# Remote.net
KiCad netlist of a schematic drawn in EAGLE
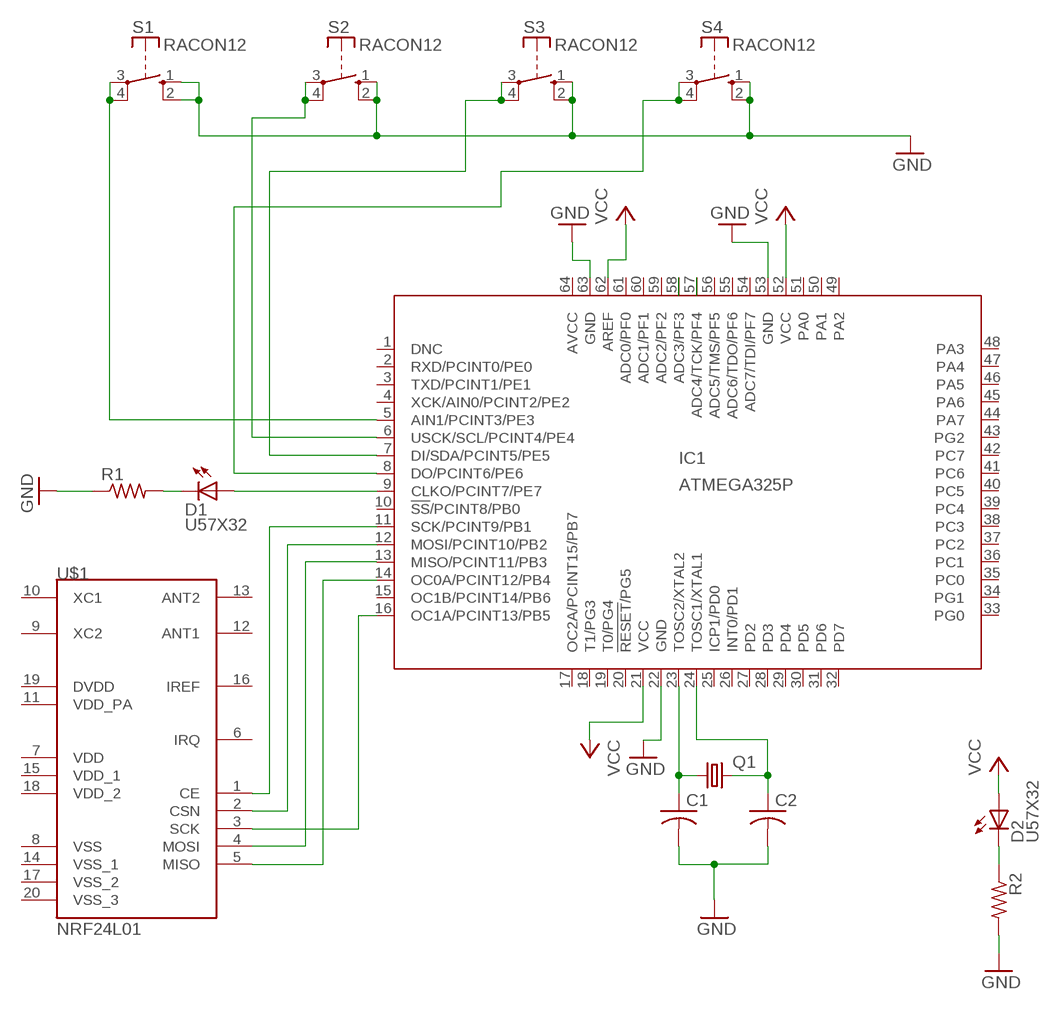
[diagram p0: schematic, sheet 1]

(export (version "E")
  (design (tool "Eeschema 10.0.6"))
  (components
    (comp (ref "C1")
      (value "C-US025-024X044")
      (footprint "eagle-import:C025-024X044")
      (libsource (lib "eagle-import") (part "C-US025-024X044"))
    )
    (comp (ref "C2")
      (value "C-US025-024X044")
      (footprint "eagle-import:C025-024X044")
      (libsource (lib "eagle-import") (part "C-US025-024X044"))
    )
    (comp (ref "D1")
      (value "U57X32")
      (footprint "eagle-import:U57X32")
      (libsource (lib "eagle-import") (part "U57X32"))
    )
    (comp (ref "D2")
      (value "U57X32")
      (footprint "eagle-import:U57X32")
      (libsource (lib "eagle-import") (part "U57X32"))
    )
    (comp (ref "IC1")
      (value "ATMEGA325P")
      (footprint "eagle-import:64M1")
      (fields (field (name "MPN") "ATMEGA325PV-10AU"))
      (libsource (lib "eagle-import") (part "ATMEGA325P"))
    )
    (comp (ref "Q1")
      (value "CRYSTALHC49S")
      (footprint "eagle-import:HC49_S")
      (libsource (lib "eagle-import") (part "CRYSTALHC49S"))
    )
    (comp (ref "R1")
      (value "R-US_0204/5")
      (footprint "eagle-import:0204_5")
      (libsource (lib "eagle-import") (part "R-US_0204/5"))
    )
    (comp (ref "R2")
      (value "R-US_0204/5")
      (footprint "eagle-import:0204_5")
      (libsource (lib "eagle-import") (part "R-US_0204/5"))
    )
    (comp (ref "S1")
      (value "RACON12")
      (footprint "eagle-import:RACON12")
      (libsource (lib "eagle-import") (part "RACON12"))
    )
    (comp (ref "S2")
      (value "RACON12")
      (footprint "eagle-import:RACON12")
      (libsource (lib "eagle-import") (part "RACON12"))
    )
    (comp (ref "S3")
      (value "RACON12")
      (footprint "eagle-import:RACON12")
      (libsource (lib "eagle-import") (part "RACON12"))
    )
    (comp (ref "S4")
      (value "RACON12")
      (footprint "eagle-import:RACON12")
      (libsource (lib "eagle-import") (part "RACON12"))
    )
    (comp (ref "U$1")
      (value "NRF24L01")
      (footprint "eagle-import:QFN20")
      (libsource (lib "eagle-import") (part "NRF24L01"))
    )
  )
  (nets
    (net (code "1") (name "/AVCC") (class "Default")
      (node (ref "IC1") (pin "64") (pinfunction "AVCC_64") (pintype "power_in"))
    )
    (net (code "2") (name "GND") (class "Default")
      (node (ref "C1") (pin "2") (pinfunction "2_2") (pintype "passive"))
      (node (ref "C2") (pin "2") (pinfunction "2_2") (pintype "passive"))
      (node (ref "IC1") (pin "22") (pinfunction "GND_22") (pintype "power_in"))
      (node (ref "IC1") (pin "53") (pinfunction "GND_53") (pintype "power_in"))
      (node (ref "IC1") (pin "63") (pinfunction "GND_63") (pintype "power_in"))
      (node (ref "R1") (pin "1") (pinfunction "1_1") (pintype "passive"))
      (node (ref "R2") (pin "2") (pinfunction "2_2") (pintype "passive"))
      (node (ref "S1") (pin "1") (pinfunction "S_1") (pintype "passive"))
      (node (ref "S1") (pin "2") (pinfunction "S_2") (pintype "passive"))
      (node (ref "S2") (pin "1") (pinfunction "S_1") (pintype "passive"))
      (node (ref "S2") (pin "2") (pinfunction "S_2") (pintype "passive"))
      (node (ref "S3") (pin "1") (pinfunction "S_1") (pintype "passive"))
      (node (ref "S3") (pin "2") (pinfunction "S_2") (pintype "passive"))
      (node (ref "S4") (pin "1") (pinfunction "S_1") (pintype "passive"))
      (node (ref "S4") (pin "2") (pinfunction "S_2") (pintype "passive"))
    )
    (net (code "3") (name "Net-(D1-C)") (class "Default")
      (node (ref "D1") (pin "K") (pinfunction "C_K") (pintype "passive"))
      (node (ref "R1") (pin "2") (pinfunction "2_2") (pintype "passive"))
    )
    (net (code "4") (name "Net-(D2-C)") (class "Default")
      (node (ref "D2") (pin "K") (pinfunction "C_K") (pintype "passive"))
      (node (ref "R2") (pin "1") (pinfunction "1_1") (pintype "passive"))
    )
    (net (code "5") (name "Net-(IC1-AIN1{slash}PCINT3{slash}PE3)") (class "Default")
      (node (ref "IC1") (pin "5") (pinfunction "AIN1/PCINT3/PE3_5") (pintype "bidirectional"))
      (node (ref "S1") (pin "3") (pinfunction "P_3") (pintype "passive"))
      (node (ref "S1") (pin "4") (pinfunction "P_4") (pintype "passive"))
    )
    (net (code "6") (name "Net-(IC1-CLKO{slash}PCINT7{slash}PE7)") (class "Default")
      (node (ref "D1") (pin "A") (pinfunction "A_A") (pintype "passive"))
      (node (ref "IC1") (pin "9") (pinfunction "CLKO/PCINT7/PE7_9") (pintype "bidirectional"))
    )
    (net (code "7") (name "Net-(IC1-DI{slash}SDA{slash}PCINT5{slash}PE5)") (class "Default")
      (node (ref "IC1") (pin "7") (pinfunction "DI/SDA/PCINT5/PE5_7") (pintype "bidirectional"))
      (node (ref "S3") (pin "3") (pinfunction "P_3") (pintype "passive"))
      (node (ref "S3") (pin "4") (pinfunction "P_4") (pintype "passive"))
    )
    (net (code "8") (name "Net-(IC1-DO{slash}PCINT6{slash}PE6)") (class "Default")
      (node (ref "IC1") (pin "8") (pinfunction "DO/PCINT6/PE6_8") (pintype "bidirectional"))
      (node (ref "S4") (pin "3") (pinfunction "P_3") (pintype "passive"))
      (node (ref "S4") (pin "4") (pinfunction "P_4") (pintype "passive"))
    )
    (net (code "9") (name "Net-(IC1-MISO{slash}PCINT11{slash}PB3)") (class "Default")
      (node (ref "IC1") (pin "13") (pinfunction "MISO/PCINT11/PB3_13") (pintype "bidirectional"))
      (node (ref "U$1") (pin "4") (pinfunction "MOSI_4") (pintype "bidirectional"))
    )
    (net (code "10") (name "Net-(IC1-MOSI{slash}PCINT10{slash}PB2)") (class "Default")
      (node (ref "IC1") (pin "12") (pinfunction "MOSI/PCINT10/PB2_12") (pintype "bidirectional"))
      (node (ref "U$1") (pin "2") (pinfunction "CSN_2") (pintype "bidirectional"))
    )
    (net (code "11") (name "Net-(IC1-OC0A{slash}PCINT12{slash}PB4)") (class "Default")
      (node (ref "IC1") (pin "14") (pinfunction "OC0A/PCINT12/PB4_14") (pintype "bidirectional"))
      (node (ref "U$1") (pin "5") (pinfunction "MISO_5") (pintype "bidirectional"))
    )
    (net (code "12") (name "Net-(IC1-OC1A{slash}PCINT13{slash}PB5)") (class "Default")
      (node (ref "IC1") (pin "16") (pinfunction "OC1A/PCINT13/PB5_16") (pintype "bidirectional"))
      (node (ref "U$1") (pin "3") (pinfunction "SCK_3") (pintype "bidirectional"))
    )
    (net (code "13") (name "Net-(IC1-SCK{slash}PCINT9{slash}PB1)") (class "Default")
      (node (ref "IC1") (pin "11") (pinfunction "SCK/PCINT9/PB1_11") (pintype "bidirectional"))
      (node (ref "U$1") (pin "1") (pinfunction "CE_1") (pintype "bidirectional"))
    )
    (net (code "14") (name "Net-(IC1-TOSC1{slash}XTAL1)") (class "Default")
      (node (ref "C2") (pin "1") (pinfunction "1_1") (pintype "passive"))
      (node (ref "IC1") (pin "24") (pinfunction "TOSC1/XTAL1_24") (pintype "input"))
      (node (ref "Q1") (pin "2") (pinfunction "2_2") (pintype "passive"))
    )
    (net (code "15") (name "Net-(IC1-TOSC2{slash}XTAL2)") (class "Default")
      (node (ref "C1") (pin "1") (pinfunction "1_1") (pintype "passive"))
      (node (ref "IC1") (pin "23") (pinfunction "TOSC2/XTAL2_23") (pintype "output"))
      (node (ref "Q1") (pin "1") (pinfunction "1_1") (pintype "passive"))
    )
    (net (code "16") (name "Net-(IC1-USCK{slash}SCL{slash}PCINT4{slash}PE4)") (class "Default")
      (node (ref "IC1") (pin "6") (pinfunction "USCK/SCL/PCINT4/PE4_6") (pintype "bidirectional"))
      (node (ref "S2") (pin "3") (pinfunction "P_3") (pintype "passive"))
      (node (ref "S2") (pin "4") (pinfunction "P_4") (pintype "passive"))
    )
    (net (code "17") (name "VCC") (class "Default")
      (node (ref "D2") (pin "A") (pinfunction "A_A") (pintype "passive"))
      (node (ref "IC1") (pin "21") (pinfunction "VCC_21") (pintype "power_in"))
      (node (ref "IC1") (pin "52") (pinfunction "VCC_52") (pintype "power_in"))
      (node (ref "IC1") (pin "62") (pinfunction "AREF_62") (pintype "input"))
    )
    (net (code "18") (name "unconnected-(IC1-ADC0{slash}PF0-Pad61)") (class "Default")
      (node (ref "IC1") (pin "61") (pinfunction "ADC0/PF0_61") (pintype "bidirectional"))
    )
    (net (code "19") (name "unconnected-(IC1-ADC1{slash}PF1-Pad60)") (class "Default")
      (node (ref "IC1") (pin "60") (pinfunction "ADC1/PF1_60") (pintype "bidirectional"))
    )
    (net (code "20") (name "unconnected-(IC1-ADC2{slash}PF2-Pad59)") (class "Default")
      (node (ref "IC1") (pin "59") (pinfunction "ADC2/PF2_59") (pintype "bidirectional"))
    )
    (net (code "21") (name "unconnected-(IC1-ADC3{slash}PF3-Pad58)") (class "Default")
      (node (ref "IC1") (pin "58") (pinfunction "ADC3/PF3_58") (pintype "bidirectional"))
    )
    (net (code "22") (name "unconnected-(IC1-ADC4{slash}TCK{slash}PF4-Pad57)") (class "Default")
      (node (ref "IC1") (pin "57") (pinfunction "ADC4/TCK/PF4_57") (pintype "bidirectional"))
    )
    (net (code "23") (name "unconnected-(IC1-ADC5{slash}TMS{slash}PF5-Pad56)") (class "Default")
      (node (ref "IC1") (pin "56") (pinfunction "ADC5/TMS/PF5_56") (pintype "bidirectional"))
    )
    (net (code "24") (name "unconnected-(IC1-ADC6{slash}TDO{slash}PF6-Pad55)") (class "Default")
      (node (ref "IC1") (pin "55") (pinfunction "ADC6/TDO/PF6_55") (pintype "bidirectional"))
    )
    (net (code "25") (name "unconnected-(IC1-ADC7{slash}TDI{slash}PF7-Pad54)") (class "Default")
      (node (ref "IC1") (pin "54") (pinfunction "ADC7/TDI/PF7_54") (pintype "bidirectional"))
    )
    (net (code "26") (name "unconnected-(IC1-DNC-Pad1)") (class "Default")
      (node (ref "IC1") (pin "1") (pinfunction "DNC_1") (pintype "input"))
    )
    (net (code "27") (name "unconnected-(IC1-ICP1{slash}PD0-Pad25)") (class "Default")
      (node (ref "IC1") (pin "25") (pinfunction "ICP1/PD0_25") (pintype "bidirectional"))
    )
    (net (code "28") (name "unconnected-(IC1-INT0{slash}PD1-Pad26)") (class "Default")
      (node (ref "IC1") (pin "26") (pinfunction "INT0/PD1_26") (pintype "bidirectional"))
    )
    (net (code "29") (name "unconnected-(IC1-OC1B{slash}PCINT14{slash}PB6-Pad15)") (class "Default")
      (node (ref "IC1") (pin "15") (pinfunction "OC1B/PCINT14/PB6_15") (pintype "bidirectional"))
    )
    (net (code "30") (name "unconnected-(IC1-OC2A{slash}PCINT15{slash}PB7-Pad17)") (class "Default")
      (node (ref "IC1") (pin "17") (pinfunction "OC2A/PCINT15/PB7_17") (pintype "bidirectional"))
    )
    (net (code "31") (name "unconnected-(IC1-PA0-Pad51)") (class "Default")
      (node (ref "IC1") (pin "51") (pinfunction "PA0_51") (pintype "bidirectional"))
    )
    (net (code "32") (name "unconnected-(IC1-PA1-Pad50)") (class "Default")
      (node (ref "IC1") (pin "50") (pinfunction "PA1_50") (pintype "bidirectional"))
    )
    (net (code "33") (name "unconnected-(IC1-PA2-Pad49)") (class "Default")
      (node (ref "IC1") (pin "49") (pinfunction "PA2_49") (pintype "bidirectional"))
    )
    (net (code "34") (name "unconnected-(IC1-PA3-Pad48)") (class "Default")
      (node (ref "IC1") (pin "48") (pinfunction "PA3_48") (pintype "bidirectional"))
    )
    (net (code "35") (name "unconnected-(IC1-PA4-Pad47)") (class "Default")
      (node (ref "IC1") (pin "47") (pinfunction "PA4_47") (pintype "bidirectional"))
    )
    (net (code "36") (name "unconnected-(IC1-PA5-Pad46)") (class "Default")
      (node (ref "IC1") (pin "46") (pinfunction "PA5_46") (pintype "bidirectional"))
    )
    (net (code "37") (name "unconnected-(IC1-PA6-Pad45)") (class "Default")
      (node (ref "IC1") (pin "45") (pinfunction "PA6_45") (pintype "bidirectional"))
    )
    (net (code "38") (name "unconnected-(IC1-PA7-Pad44)") (class "Default")
      (node (ref "IC1") (pin "44") (pinfunction "PA7_44") (pintype "bidirectional"))
    )
    (net (code "39") (name "unconnected-(IC1-PC0-Pad35)") (class "Default")
      (node (ref "IC1") (pin "35") (pinfunction "PC0_35") (pintype "bidirectional"))
    )
    (net (code "40") (name "unconnected-(IC1-PC1-Pad36)") (class "Default")
      (node (ref "IC1") (pin "36") (pinfunction "PC1_36") (pintype "bidirectional"))
    )
    (net (code "41") (name "unconnected-(IC1-PC2-Pad37)") (class "Default")
      (node (ref "IC1") (pin "37") (pinfunction "PC2_37") (pintype "bidirectional"))
    )
    (net (code "42") (name "unconnected-(IC1-PC3-Pad38)") (class "Default")
      (node (ref "IC1") (pin "38") (pinfunction "PC3_38") (pintype "bidirectional"))
    )
    (net (code "43") (name "unconnected-(IC1-PC4-Pad39)") (class "Default")
      (node (ref "IC1") (pin "39") (pinfunction "PC4_39") (pintype "bidirectional"))
    )
    (net (code "44") (name "unconnected-(IC1-PC5-Pad40)") (class "Default")
      (node (ref "IC1") (pin "40") (pinfunction "PC5_40") (pintype "bidirectional"))
    )
    (net (code "45") (name "unconnected-(IC1-PC6-Pad41)") (class "Default")
      (node (ref "IC1") (pin "41") (pinfunction "PC6_41") (pintype "bidirectional"))
    )
    (net (code "46") (name "unconnected-(IC1-PC7-Pad42)") (class "Default")
      (node (ref "IC1") (pin "42") (pinfunction "PC7_42") (pintype "bidirectional"))
    )
    (net (code "47") (name "unconnected-(IC1-PD2-Pad27)") (class "Default")
      (node (ref "IC1") (pin "27") (pinfunction "PD2_27") (pintype "bidirectional"))
    )
    (net (code "48") (name "unconnected-(IC1-PD3-Pad28)") (class "Default")
      (node (ref "IC1") (pin "28") (pinfunction "PD3_28") (pintype "bidirectional"))
    )
    (net (code "49") (name "unconnected-(IC1-PD4-Pad29)") (class "Default")
      (node (ref "IC1") (pin "29") (pinfunction "PD4_29") (pintype "bidirectional"))
    )
    (net (code "50") (name "unconnected-(IC1-PD5-Pad30)") (class "Default")
      (node (ref "IC1") (pin "30") (pinfunction "PD5_30") (pintype "bidirectional"))
    )
    (net (code "51") (name "unconnected-(IC1-PD6-Pad31)") (class "Default")
      (node (ref "IC1") (pin "31") (pinfunction "PD6_31") (pintype "bidirectional"))
    )
    (net (code "52") (name "unconnected-(IC1-PD7-Pad32)") (class "Default")
      (node (ref "IC1") (pin "32") (pinfunction "PD7_32") (pintype "bidirectional"))
    )
    (net (code "53") (name "unconnected-(IC1-PG0-Pad33)") (class "Default")
      (node (ref "IC1") (pin "33") (pinfunction "PG0_33") (pintype "bidirectional"))
    )
    (net (code "54") (name "unconnected-(IC1-PG1-Pad34)") (class "Default")
      (node (ref "IC1") (pin "34") (pinfunction "PG1_34") (pintype "bidirectional"))
    )
    (net (code "55") (name "unconnected-(IC1-PG2-Pad43)") (class "Default")
      (node (ref "IC1") (pin "43") (pinfunction "PG2_43") (pintype "bidirectional"))
    )
    (net (code "56") (name "unconnected-(IC1-RXD{slash}PCINT0{slash}PE0-Pad2)") (class "Default")
      (node (ref "IC1") (pin "2") (pinfunction "RXD/PCINT0/PE0_2") (pintype "bidirectional"))
    )
    (net (code "57") (name "unconnected-(IC1-T0{slash}PG4-Pad19)") (class "Default")
      (node (ref "IC1") (pin "19") (pinfunction "T0/PG4_19") (pintype "bidirectional"))
    )
    (net (code "58") (name "unconnected-(IC1-T1{slash}PG3-Pad18)") (class "Default")
      (node (ref "IC1") (pin "18") (pinfunction "T1/PG3_18") (pintype "bidirectional"))
    )
    (net (code "59") (name "unconnected-(IC1-TXD{slash}PCINT1{slash}PE1-Pad3)") (class "Default")
      (node (ref "IC1") (pin "3") (pinfunction "TXD/PCINT1/PE1_3") (pintype "bidirectional"))
    )
    (net (code "60") (name "unconnected-(IC1-XCK{slash}AIN0{slash}PCINT2{slash}PE2-Pad4)") (class "Default")
      (node (ref "IC1") (pin "4") (pinfunction "XCK/AIN0/PCINT2/PE2_4") (pintype "bidirectional"))
    )
    (net (code "61") (name "unconnected-(IC1-~{RESET}{slash}PG5-Pad20)") (class "Default")
      (node (ref "IC1") (pin "20") (pinfunction "~{RESET}/PG5_20") (pintype "input"))
    )
    (net (code "62") (name "unconnected-(IC1-~{SS}{slash}PCINT8{slash}PB0-Pad10)") (class "Default")
      (node (ref "IC1") (pin "10") (pinfunction "~{SS}/PCINT8/PB0_10") (pintype "bidirectional"))
    )
    (net (code "63") (name "unconnected-(U$1-ANT1-Pad12)") (class "Default")
      (node (ref "U$1") (pin "12") (pinfunction "ANT1_12") (pintype "bidirectional"))
    )
    (net (code "64") (name "unconnected-(U$1-ANT2-Pad13)") (class "Default")
      (node (ref "U$1") (pin "13") (pinfunction "ANT2_13") (pintype "bidirectional"))
    )
    (net (code "65") (name "unconnected-(U$1-DVDD-Pad19)") (class "Default")
      (node (ref "U$1") (pin "19") (pinfunction "DVDD_19") (pintype "bidirectional"))
    )
    (net (code "66") (name "unconnected-(U$1-IREF-Pad16)") (class "Default")
      (node (ref "U$1") (pin "16") (pinfunction "IREF_16") (pintype "bidirectional"))
    )
    (net (code "67") (name "unconnected-(U$1-IRQ-Pad6)") (class "Default")
      (node (ref "U$1") (pin "6") (pinfunction "IRQ_6") (pintype "bidirectional"))
    )
    (net (code "68") (name "unconnected-(U$1-VDD-Pad7)") (class "Default")
      (node (ref "U$1") (pin "7") (pinfunction "VDD_7") (pintype "bidirectional"))
    )
    (net (code "69") (name "unconnected-(U$1-VDD_1-Pad15)") (class "Default")
      (node (ref "U$1") (pin "15") (pinfunction "VDD_1_15") (pintype "bidirectional"))
    )
    (net (code "70") (name "unconnected-(U$1-VDD_2-Pad18)") (class "Default")
      (node (ref "U$1") (pin "18") (pinfunction "VDD_2_18") (pintype "bidirectional"))
    )
    (net (code "71") (name "unconnected-(U$1-VDD_PA-Pad11)") (class "Default")
      (node (ref "U$1") (pin "11") (pinfunction "VDD_PA_11") (pintype "bidirectional"))
    )
    (net (code "72") (name "unconnected-(U$1-VSS-Pad8)") (class "Default")
      (node (ref "U$1") (pin "8") (pinfunction "VSS_8") (pintype "bidirectional"))
    )
    (net (code "73") (name "unconnected-(U$1-VSS_1-Pad14)") (class "Default")
      (node (ref "U$1") (pin "14") (pinfunction "VSS_1_14") (pintype "bidirectional"))
    )
    (net (code "74") (name "unconnected-(U$1-VSS_2-Pad17)") (class "Default")
      (node (ref "U$1") (pin "17") (pinfunction "VSS_2_17") (pintype "bidirectional"))
    )
    (net (code "75") (name "unconnected-(U$1-VSS_3-Pad20)") (class "Default")
      (node (ref "U$1") (pin "20") (pinfunction "VSS_3_20") (pintype "bidirectional"))
    )
    (net (code "76") (name "unconnected-(U$1-XC1-Pad10)") (class "Default")
      (node (ref "U$1") (pin "10") (pinfunction "XC1_10") (pintype "bidirectional"))
    )
    (net (code "77") (name "unconnected-(U$1-XC2-Pad9)") (class "Default")
      (node (ref "U$1") (pin "9") (pinfunction "XC2_9") (pintype "bidirectional"))
    )
  )
)
